# EngineeringModelBoard.net
KiCad netlist of a schematic drawn in EAGLE
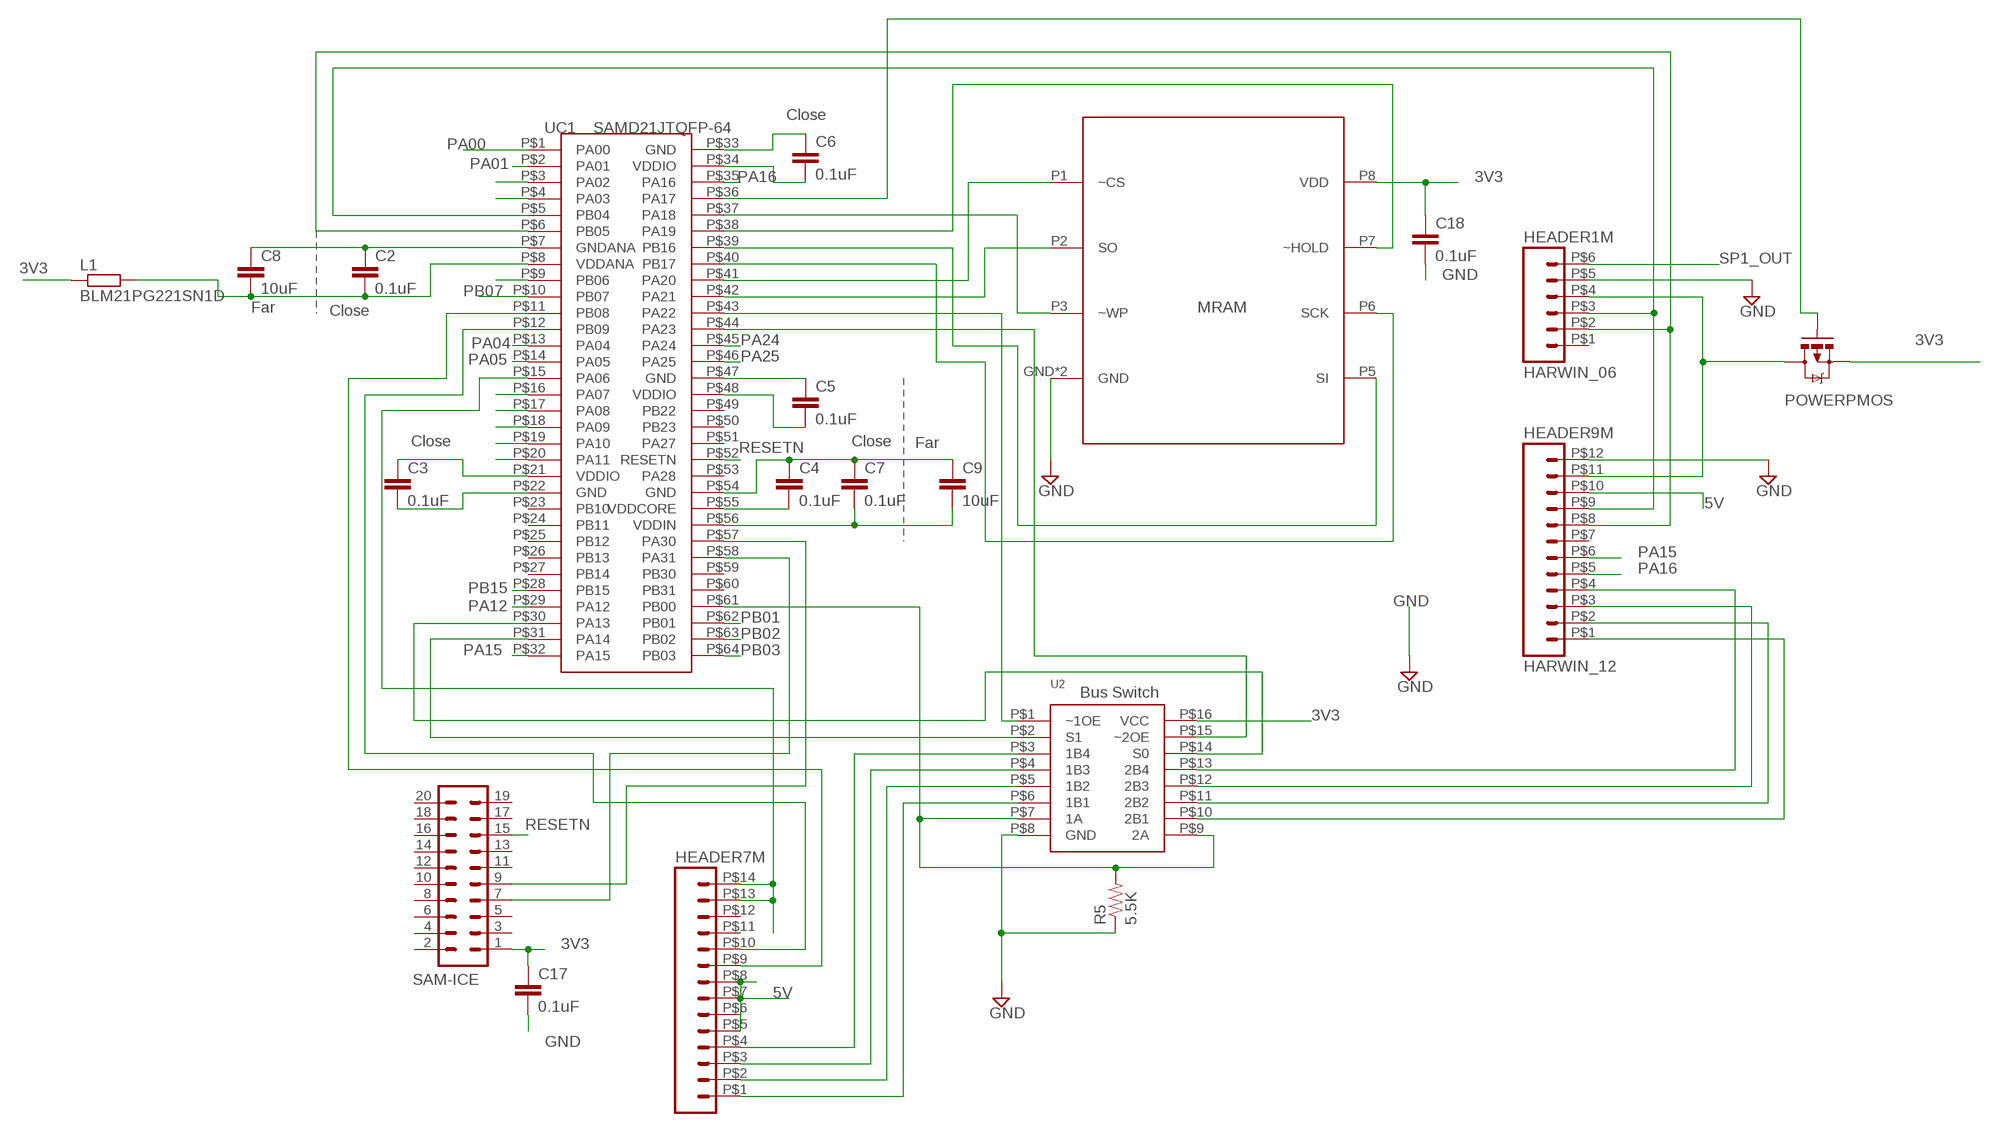
[diagram p0: schematic, sheet 1]
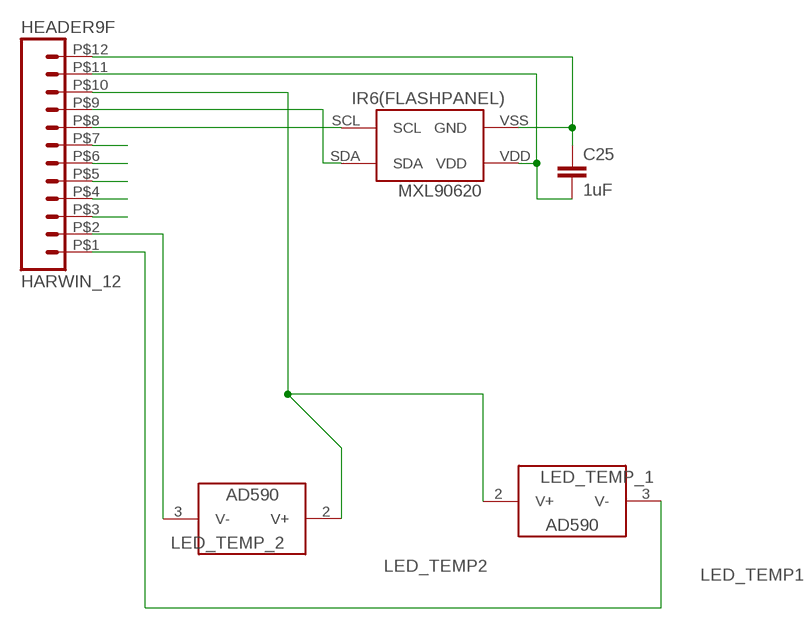
[diagram p1: schematic, sheet 2]
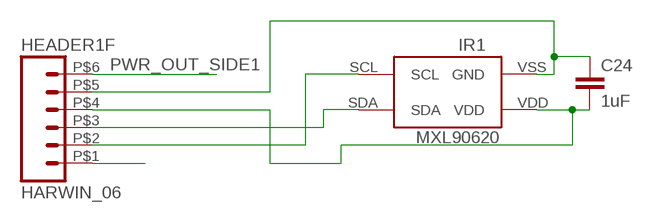
[diagram p2: schematic, sheet 3]
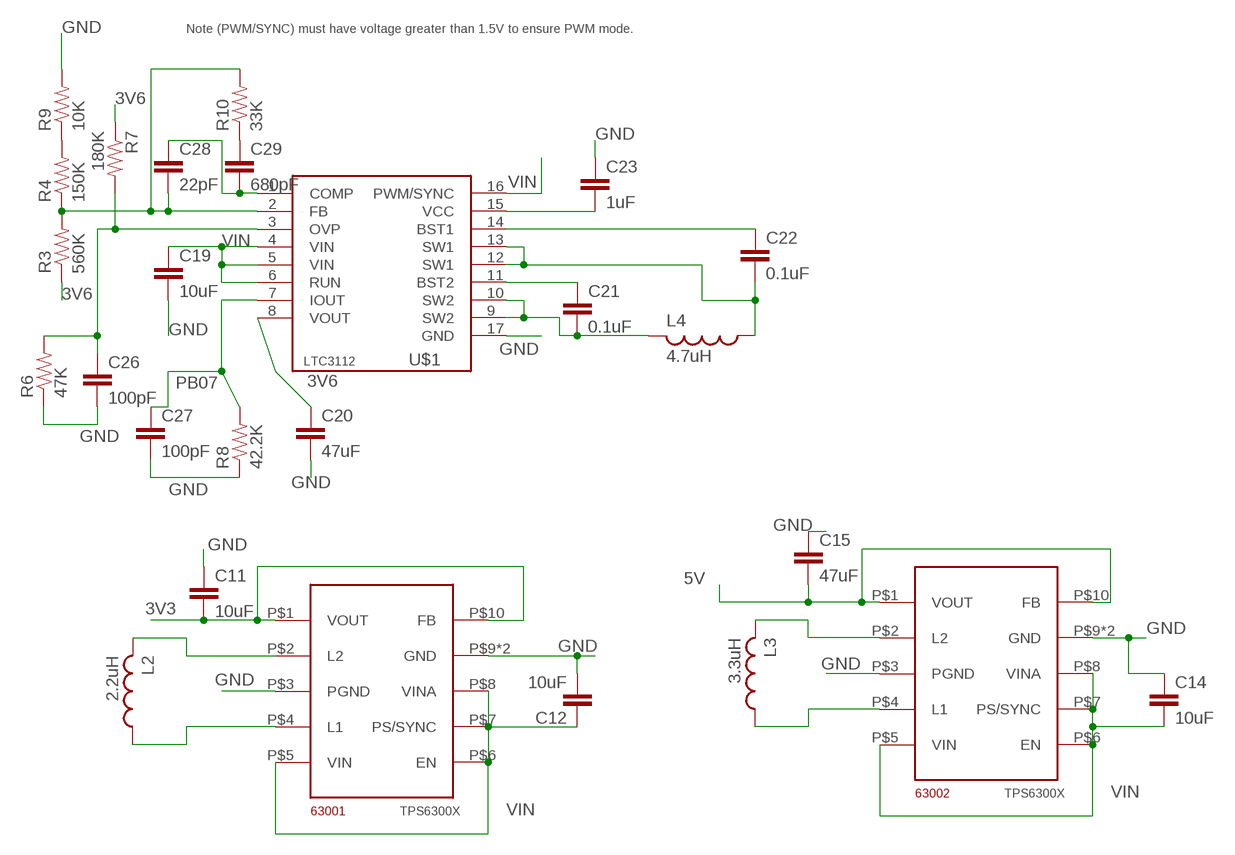
[diagram p3: schematic, sheet 4]
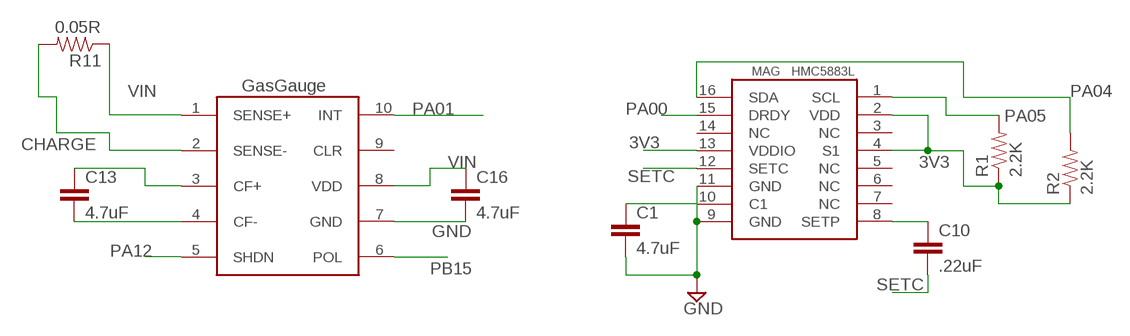
[diagram p4: schematic, sheet 5]
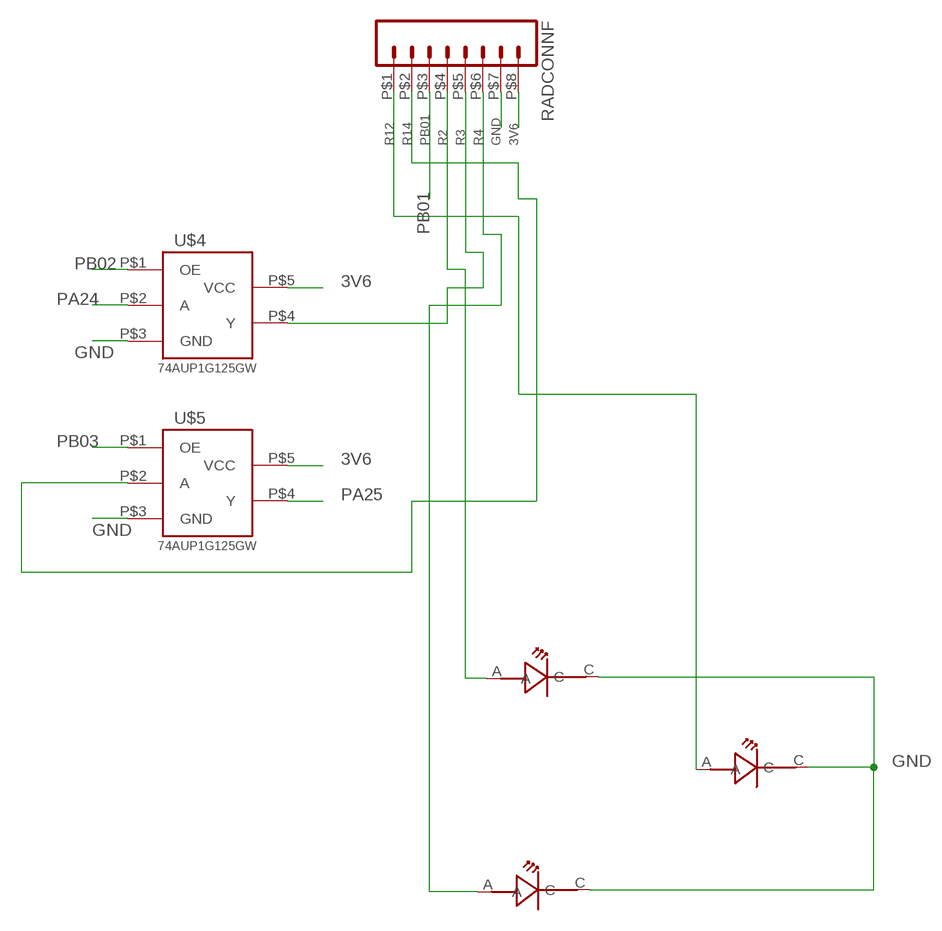
[diagram p5: schematic, sheet 6]
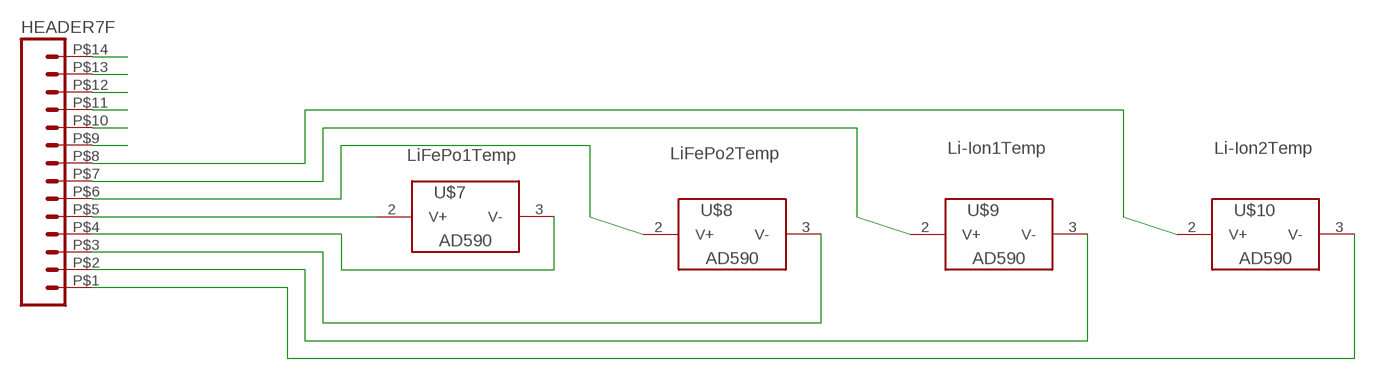
[diagram p6: schematic, sheet 7]

(export (version "E")
  (design (tool "Eeschema 10.0.6"))
  (components
    (comp (ref "C25")
      (value "1uF")
      (footprint "eagle-import:0805")
      (fields (field (name "MPN") "0805ZC105KAT2A"))
      (libsource (lib "eagle-import") (part "CAP0805"))
    )
    (comp (ref "HEADER9F")
      (value "HARWIN_12")
      (footprint "eagle-import:HARWIN_DATAMATE_12")
      (libsource (lib "eagle-import") (part "HARWIN_12"))
    )
    (comp (ref "IR6(FLASHPANEL)")
      (value "MXL90620")
      (footprint "eagle-import:MXL90620")
      (libsource (lib "eagle-import") (part "MXL90620"))
    )
    (comp (ref "LED_TEMP_1")
      (value "AD590-SOIC-8")
      (footprint "eagle-import:8SOIC")
      (fields (field (name "MPN") "AD590JRZ"))
      (libsource (lib "eagle-import") (part "AD590-SOIC-8"))
    )
    (comp (ref "LED_TEMP_2")
      (value "AD590-SOIC-8")
      (footprint "eagle-import:8SOIC")
      (fields (field (name "MPN") "AD590JRZ"))
      (libsource (lib "eagle-import") (part "AD590-SOIC-8"))
    )
    (comp (ref "RADCONNF")
      (value "HARWIN_08")
      (footprint "eagle-import:HARWIN_DATAMATE_08")
      (libsource (lib "eagle-import") (part "HARWIN_08"))
    )
    (comp (ref "U$4")
      (value "74AUP1G125GW")
      (footprint "eagle-import:TSSOP-5")
      (libsource (lib "eagle-import") (part "74AUP1G125GW"))
    )
    (comp (ref "U$5")
      (value "74AUP1G125GW")
      (footprint "eagle-import:TSSOP-5")
      (libsource (lib "eagle-import") (part "74AUP1G125GW"))
    )
    (comp (ref "U$11")
      (value "LT-T673-Q1R2-25-Z")
      (footprint "eagle-import:PLCC-2")
      (libsource (lib "eagle-import") (part "LT-T673-Q1R2-25-Z"))
    )
    (comp (ref "U$12")
      (value "LT-T673-Q1R2-25-Z")
      (footprint "eagle-import:PLCC-2")
      (libsource (lib "eagle-import") (part "LT-T673-Q1R2-25-Z"))
    )
    (comp (ref "U$13")
      (value "LT-T673-Q1R2-25-Z")
      (footprint "eagle-import:PLCC-2")
      (libsource (lib "eagle-import") (part "LT-T673-Q1R2-25-Z"))
    )
    (comp (ref "HEADER7F")
      (value "HARWIN_14")
      (footprint "eagle-import:HARWIN_DATAMATE_14")
      (libsource (lib "eagle-import") (part "HARWIN_14"))
    )
    (comp (ref "U$7")
      (value "AD590-SOIC-8")
      (footprint "eagle-import:8SOIC")
      (fields (field (name "MPN") "AD590JRZ"))
      (libsource (lib "eagle-import") (part "AD590-SOIC-8"))
    )
    (comp (ref "U$8")
      (value "AD590-SOIC-8")
      (footprint "eagle-import:8SOIC")
      (fields (field (name "MPN") "AD590JRZ"))
      (libsource (lib "eagle-import") (part "AD590-SOIC-8"))
    )
    (comp (ref "U$9")
      (value "AD590-SOIC-8")
      (footprint "eagle-import:8SOIC")
      (fields (field (name "MPN") "AD590JRZ"))
      (libsource (lib "eagle-import") (part "AD590-SOIC-8"))
    )
    (comp (ref "U$10")
      (value "AD590-SOIC-8")
      (footprint "eagle-import:8SOIC")
      (fields (field (name "MPN") "AD590JRZ"))
      (libsource (lib "eagle-import") (part "AD590-SOIC-8"))
    )
    (comp (ref "C1")
      (value "4.7uF")
      (footprint "eagle-import:0805")
      (fields (field (name "MF") "AVX CORPORATION") (field (name "MPN") "08056D475KAT2A"))
      (libsource (lib "eagle-import") (part "CAP0805"))
    )
    (comp (ref "C10")
      (value ".22uF")
      (footprint "eagle-import:0805")
      (fields (field (name "MF") "AVX CORPORATION") (field (name "MPN") "08053C224KAT2A"))
      (libsource (lib "eagle-import") (part "CAP0805"))
    )
    (comp (ref "C13")
      (value "4.7uF")
      (footprint "eagle-import:0805")
      (fields (field (name "MF") "AVX CORPORATION") (field (name "MPN") "08056D475KAT2A"))
      (libsource (lib "eagle-import") (part "CAP0805"))
    )
    (comp (ref "C16")
      (value "4.7uF")
      (footprint "eagle-import:0805")
      (fields (field (name "MF") "AVX CORPORATION") (field (name "MPN") "08056D475KAT2A"))
      (libsource (lib "eagle-import") (part "CAP0805"))
    )
    (comp (ref "MAG")
      (value "HMC5883L")
      (footprint "eagle-import:HMC5883L")
      (fields (field (name "MPN") "HMC5883L-TR"))
      (libsource (lib "eagle-import") (part "HMC5883L"))
    )
    (comp (ref "R1")
      (value "2.2K")
      (footprint "eagle-import:0805")
      (fields (field (name "MPN") "SR1-0805-222"))
      (libsource (lib "eagle-import") (part "RESISTOR"))
    )
    (comp (ref "R2")
      (value "2.2K")
      (footprint "eagle-import:0805")
      (fields (field (name "MPN") "SR1-0805-222"))
      (libsource (lib "eagle-import") (part "RESISTOR"))
    )
    (comp (ref "R11")
      (value "0.05R")
      (footprint "eagle-import:0805")
      (libsource (lib "eagle-import") (part "RESISTOR"))
    )
    (comp (ref "U$2")
      (value "LTC4150")
      (footprint "eagle-import:MSOP10")
      (fields (field (name "MPN") "LTC4150CMS#PBF"))
      (libsource (lib "eagle-import") (part "LTC4150"))
    )
    (comp (ref "C24")
      (value "1uF")
      (footprint "eagle-import:0805")
      (fields (field (name "MPN") "0805ZC105KAT2A"))
      (libsource (lib "eagle-import") (part "CAP0805"))
    )
    (comp (ref "HEADER1F")
      (value "HARWIN_06")
      (footprint "eagle-import:HARWIN_DATAMATE_6")
      (libsource (lib "eagle-import") (part "HARWIN_06"))
    )
    (comp (ref "IR1")
      (value "MXL90620")
      (footprint "eagle-import:MXL90620")
      (libsource (lib "eagle-import") (part "MXL90620"))
    )
    (comp (ref "C2")
      (value "0.1uF")
      (footprint "eagle-import:0805")
      (fields (field (name "MPN") "0603YC104JAT2A"))
      (libsource (lib "eagle-import") (part "CAP0805"))
    )
    (comp (ref "C3")
      (value "0.1uF")
      (footprint "eagle-import:0805")
      (fields (field (name "MPN") "0603YC104JAT2A"))
      (libsource (lib "eagle-import") (part "CAP0805"))
    )
    (comp (ref "C4")
      (value "0.1uF")
      (footprint "eagle-import:0805")
      (fields (field (name "MPN") "0603YC104JAT2A"))
      (libsource (lib "eagle-import") (part "CAP0805"))
    )
    (comp (ref "C5")
      (value "0.1uF")
      (footprint "eagle-import:0805")
      (fields (field (name "MPN") "0603YC104JAT2A"))
      (libsource (lib "eagle-import") (part "CAP0805"))
    )
    (comp (ref "C6")
      (value "0.1uF")
      (footprint "eagle-import:0805")
      (fields (field (name "MPN") "0603YC104JAT2A"))
      (libsource (lib "eagle-import") (part "CAP0805"))
    )
    (comp (ref "C7")
      (value "0.1uF")
      (footprint "eagle-import:0805")
      (fields (field (name "MPN") "0603YC104JAT2A"))
      (libsource (lib "eagle-import") (part "CAP0805"))
    )
    (comp (ref "C8")
      (value "10uF")
      (footprint "eagle-import:0805")
      (fields (field (name "MF") "AVX CORPORATION") (field (name "MPN") "08056D106KAT2A"))
      (libsource (lib "eagle-import") (part "CAP0805"))
    )
    (comp (ref "C9")
      (value "10uF")
      (footprint "eagle-import:0805")
      (fields (field (name "MF") "AVX CORPORATION") (field (name "MPN") "08056D106KAT2A"))
      (libsource (lib "eagle-import") (part "CAP0805"))
    )
    (comp (ref "C17")
      (value "0.1uF")
      (footprint "eagle-import:0805")
      (fields (field (name "MPN") "0603YC104JAT2A"))
      (libsource (lib "eagle-import") (part "CAP0805"))
    )
    (comp (ref "C18")
      (value "0.1uF")
      (footprint "eagle-import:0805")
      (fields (field (name "MPN") "0603YC104JAT2A"))
      (libsource (lib "eagle-import") (part "CAP0805"))
    )
    (comp (ref "HEADER1M")
      (value "HARWIN_06")
      (footprint "eagle-import:HARWIN_DATAMATE_6")
      (libsource (lib "eagle-import") (part "HARWIN_06"))
    )
    (comp (ref "HEADER7M")
      (value "HARWIN_14")
      (footprint "eagle-import:HARWIN_DATAMATE_14")
      (libsource (lib "eagle-import") (part "HARWIN_14"))
    )
    (comp (ref "HEADER9M")
      (value "HARWIN_12")
      (footprint "eagle-import:HARWIN_DATAMATE_12")
      (libsource (lib "eagle-import") (part "HARWIN_12"))
    )
    (comp (ref "L1")
      (value "BLM21PG221SN1D")
      (footprint "eagle-import:R0805")
      (libsource (lib "eagle-import") (part "R-EU_R0805"))
    )
    (comp (ref "R5")
      (value "5.5K")
      (footprint "eagle-import:0805")
      (libsource (lib "eagle-import") (part "RESISTOR"))
    )
    (comp (ref "SAM-ICE")
      (value "IDC_JTAG_CONNECTOR")
      (footprint "eagle-import:2X10")
      (libsource (lib "eagle-import") (part "IDC_JTAG_CONNECTOR"))
    )
    (comp (ref "U$3")
      (value "MRAM")
      (footprint "eagle-import:8PXMO-229")
      (libsource (lib "eagle-import") (part "MR25H10CDC"))
    )
    (comp (ref "U$14")
      (value "POWERPMOS")
      (footprint "eagle-import:SO08")
      (libsource (lib "eagle-import") (part "POWERPMOS"))
    )
    (comp (ref "U2")
      (value "SN74CBTLV3253")
      (footprint "eagle-import:SOIC16R")
      (libsource (lib "eagle-import") (part "SN74CBTLV3253"))
    )
    (comp (ref "UC1")
      (value "SAMD21JTQFP-64")
      (footprint "eagle-import:TQFP-64")
      (libsource (lib "eagle-import") (part "SAMD21JTQFP-64"))
    )
    (comp (ref "63001")
      (value "TPS6300X")
      (footprint "eagle-import:QFN10_POWERPAD")
      (libsource (lib "eagle-import") (part "TPS6300X"))
    )
    (comp (ref "63002")
      (value "TPS6300X")
      (footprint "eagle-import:QFN10_POWERPAD")
      (libsource (lib "eagle-import") (part "TPS6300X"))
    )
    (comp (ref "C11")
      (value "10uF")
      (footprint "eagle-import:0603-CAP")
      (libsource (lib "eagle-import") (part "CAP0603-CAP"))
    )
    (comp (ref "C12")
      (value "10uF")
      (footprint "eagle-import:0603-CAP")
      (libsource (lib "eagle-import") (part "CAP0603-CAP"))
    )
    (comp (ref "C14")
      (value "10uF")
      (footprint "eagle-import:0603-CAP")
      (fields (field (name "MPN") "C1608X5R1A225K080AC"))
      (libsource (lib "eagle-import") (part "CAP0603-CAP"))
    )
    (comp (ref "C15")
      (value "47uF")
      (footprint "eagle-import:0603-CAP")
      (fields (field (name "MPN") "EMK107B7474KA-T"))
      (libsource (lib "eagle-import") (part "CAP0603-CAP"))
    )
    (comp (ref "C19")
      (value "10uF")
      (footprint "eagle-import:0603-CAP")
      (libsource (lib "eagle-import") (part "CAP0603-CAP"))
    )
    (comp (ref "C20")
      (value "47uF")
      (footprint "eagle-import:0805")
      (fields (field (name "MPN") "EMK107B7474KA-T"))
      (libsource (lib "eagle-import") (part "CAP0805"))
    )
    (comp (ref "C21")
      (value "0.1uF")
      (footprint "eagle-import:0603-CAP")
      (fields (field (name "MPN") "0603YC104JAT2A"))
      (libsource (lib "eagle-import") (part "CAP0603-CAP"))
    )
    (comp (ref "C22")
      (value "0.1uF")
      (footprint "eagle-import:0603-CAP")
      (fields (field (name "MPN") "0603YC104JAT2A"))
      (libsource (lib "eagle-import") (part "CAP0603-CAP"))
    )
    (comp (ref "C23")
      (value "1uF")
      (footprint "eagle-import:0603-CAP")
      (libsource (lib "eagle-import") (part "CAP0603-CAP"))
    )
    (comp (ref "C26")
      (value "100pF")
      (footprint "eagle-import:0805")
      (fields (field (name "MF") "AVX CORPORATION") (field (name "MPN") "08051A101J4T4A"))
      (libsource (lib "eagle-import") (part "CAP0805"))
    )
    (comp (ref "C27")
      (value "100pF")
      (footprint "eagle-import:0805")
      (fields (field (name "MF") "AVX CORPORATION") (field (name "MPN") "08051A101J4T4A"))
      (libsource (lib "eagle-import") (part "CAP0805"))
    )
    (comp (ref "C28")
      (value "22pF")
      (footprint "eagle-import:0805")
      (fields (field (name "MF") "AVX CORPORATION") (field (name "MPN") "08051A220JAT2A"))
      (libsource (lib "eagle-import") (part "CAP0805"))
    )
    (comp (ref "C29")
      (value "680pF")
      (footprint "eagle-import:0805")
      (fields (field (name "MPN") "08055C681KAT2A"))
      (libsource (lib "eagle-import") (part "CAP0805"))
    )
    (comp (ref "L2")
      (value "2.2uH")
      (footprint "eagle-import:L3225M")
      (libsource (lib "eagle-import") (part "L-USL3225M"))
    )
    (comp (ref "L3")
      (value "3.3uH")
      (footprint "eagle-import:L3225M")
      (fields (field (name "MPN") "JMK212BJ335KG-T"))
      (libsource (lib "eagle-import") (part "L-USL3225M"))
    )
    (comp (ref "L4")
      (value "4.7uH")
      (footprint "eagle-import:L3225M")
      (libsource (lib "eagle-import") (part "L-USL3225M"))
    )
    (comp (ref "R3")
      (value "560K")
      (footprint "eagle-import:0805")
      (fields (field (name "MPN") "MC01W08051560K"))
      (libsource (lib "eagle-import") (part "RESISTOR"))
    )
    (comp (ref "R4")
      (value "150K")
      (footprint "eagle-import:0805")
      (libsource (lib "eagle-import") (part "RESISTOR"))
    )
    (comp (ref "R6")
      (value "47K")
      (footprint "eagle-import:0805")
      (libsource (lib "eagle-import") (part "RESISTOR"))
    )
    (comp (ref "R7")
      (value "180K")
      (footprint "eagle-import:0805")
      (fields (field (name "MPN") "ERJ-6GEYJ184V"))
      (libsource (lib "eagle-import") (part "RESISTOR"))
    )
    (comp (ref "R8")
      (value "42.2K")
      (footprint "eagle-import:0805")
      (libsource (lib "eagle-import") (part "RESISTOR"))
    )
    (comp (ref "R9")
      (value "10K")
      (footprint "eagle-import:0805")
      (libsource (lib "eagle-import") (part "RESISTOR"))
    )
    (comp (ref "R10")
      (value "33K")
      (footprint "eagle-import:0805")
      (libsource (lib "eagle-import") (part "RESISTOR"))
    )
    (comp (ref "U$1")
      (value "LTC3112")
      (footprint "eagle-import:DHD16")
      (fields (field (name "MPN") "LTC3112EFE#PBF"))
      (libsource (lib "eagle-import") (part "LTC3112"))
    )
  )
  (nets
    (net (code "1") (name "3V3") (class "Default")
      (node (ref "63001") (pin "P$1") (pinfunction "VOUT_P$1") (pintype "output"))
      (node (ref "63001") (pin "P$10") (pinfunction "FB_P$10") (pintype "input"))
      (node (ref "C11") (pin "2") (pinfunction "2_2") (pintype "passive"))
      (node (ref "C17") (pin "1") (pinfunction "1_1") (pintype "passive"))
      (node (ref "C18") (pin "1") (pinfunction "1_1") (pintype "passive"))
      (node (ref "C3") (pin "1") (pinfunction "1_1") (pintype "passive"))
      (node (ref "C5") (pin "2") (pinfunction "2_2") (pintype "passive"))
      (node (ref "C6") (pin "2") (pinfunction "2_2") (pintype "passive"))
      (node (ref "C7") (pin "2") (pinfunction "2_2") (pintype "passive"))
      (node (ref "C9") (pin "2") (pinfunction "2_2") (pintype "passive"))
      (node (ref "L1") (pin "1") (pinfunction "1_1") (pintype "passive"))
      (node (ref "MAG") (pin "13") (pinfunction "VDDIO_13") (pintype "bidirectional"))
      (node (ref "MAG") (pin "2") (pinfunction "VDD_2") (pintype "bidirectional"))
      (node (ref "MAG") (pin "4") (pinfunction "S1_4") (pintype "bidirectional"))
      (node (ref "R1") (pin "1") (pinfunction "1_1") (pintype "passive"))
      (node (ref "R2") (pin "1") (pinfunction "1_1") (pintype "passive"))
      (node (ref "SAM-ICE") (pin "1") (pinfunction "1_1") (pintype "passive"))
      (node (ref "U$14") (pin "1") (pinfunction "S_1") (pintype "passive"))
      (node (ref "U$14") (pin "2") (pinfunction "S_2") (pintype "passive"))
      (node (ref "U$14") (pin "3") (pinfunction "S_3") (pintype "passive"))
      (node (ref "U$3") (pin "P8") (pinfunction "VDD_P8") (pintype "bidirectional"))
      (node (ref "U2") (pin "P$16") (pinfunction "VCC_P$16") (pintype "bidirectional"))
      (node (ref "UC1") (pin "P$21") (pinfunction "VDDIO_P$21") (pintype "power_in"))
      (node (ref "UC1") (pin "P$34") (pinfunction "VDDIO_P$34") (pintype "power_in"))
      (node (ref "UC1") (pin "P$48") (pinfunction "VDDIO_P$48") (pintype "power_in"))
      (node (ref "UC1") (pin "P$56") (pinfunction "VDDIN_P$56") (pintype "power_in"))
    )
    (net (code "2") (name "3V6") (class "Default")
      (node (ref "C20") (pin "1") (pinfunction "1_1") (pintype "passive"))
      (node (ref "R3") (pin "1") (pinfunction "1_1") (pintype "passive"))
      (node (ref "R7") (pin "1") (pinfunction "1_1") (pintype "passive"))
      (node (ref "RADCONNF") (pin "P$8") (pinfunction "8_P$8") (pintype "passive"))
      (node (ref "U$1") (pin "8") (pinfunction "VOUT_8") (pintype "bidirectional"))
      (node (ref "U$4") (pin "P$5") (pinfunction "VCC_P$5") (pintype "bidirectional"))
      (node (ref "U$5") (pin "P$5") (pinfunction "VCC_P$5") (pintype "bidirectional"))
    )
    (net (code "3") (name "5V") (class "Default")
      (node (ref "63002") (pin "P$1") (pinfunction "VOUT_P$1") (pintype "output"))
      (node (ref "63002") (pin "P$10") (pinfunction "FB_P$10") (pintype "input"))
      (node (ref "C15") (pin "2") (pinfunction "2_2") (pintype "passive"))
      (node (ref "HEADER7M") (pin "P$5") (pinfunction "5_P$5") (pintype "passive"))
      (node (ref "HEADER7M") (pin "P$6") (pinfunction "6_P$6") (pintype "passive"))
      (node (ref "HEADER7M") (pin "P$7") (pinfunction "7_P$7") (pintype "passive"))
      (node (ref "HEADER7M") (pin "P$8") (pinfunction "8_P$8") (pintype "passive"))
      (node (ref "HEADER9M") (pin "P$10") (pinfunction "10_P$10") (pintype "passive"))
    )
    (net (code "4") (name "CHARGE") (class "Default")
      (node (ref "R11") (pin "2") (pinfunction "2_2") (pintype "passive"))
      (node (ref "U$2") (pin "2") (pinfunction "SENSE-_2") (pintype "bidirectional"))
    )
    (net (code "5") (name "GND") (class "Default")
      (node (ref "63001") (pin "P$3") (pinfunction "PGND_P$3") (pintype "input"))
      (node (ref "63001") (pin "P$9") (pinfunction "GND_P$9") (pintype "input"))
      (node (ref "63001") (pin "PAD") (pinfunction "GND_PAD") (pintype "input"))
      (node (ref "63002") (pin "P$3") (pinfunction "PGND_P$3") (pintype "input"))
      (node (ref "63002") (pin "P$9") (pinfunction "GND_P$9") (pintype "input"))
      (node (ref "63002") (pin "PAD") (pinfunction "GND_PAD") (pintype "input"))
      (node (ref "C1") (pin "2") (pinfunction "2_2") (pintype "passive"))
      (node (ref "C11") (pin "1") (pinfunction "1_1") (pintype "passive"))
      (node (ref "C12") (pin "2") (pinfunction "2_2") (pintype "passive"))
      (node (ref "C14") (pin "1") (pinfunction "1_1") (pintype "passive"))
      (node (ref "C15") (pin "1") (pinfunction "1_1") (pintype "passive"))
      (node (ref "C16") (pin "2") (pinfunction "2_2") (pintype "passive"))
      (node (ref "C17") (pin "2") (pinfunction "2_2") (pintype "passive"))
      (node (ref "C18") (pin "2") (pinfunction "2_2") (pintype "passive"))
      (node (ref "C19") (pin "2") (pinfunction "2_2") (pintype "passive"))
      (node (ref "C2") (pin "1") (pinfunction "1_1") (pintype "passive"))
      (node (ref "C20") (pin "2") (pinfunction "2_2") (pintype "passive"))
      (node (ref "C23") (pin "1") (pinfunction "1_1") (pintype "passive"))
      (node (ref "C26") (pin "2") (pinfunction "2_2") (pintype "passive"))
      (node (ref "C27") (pin "2") (pinfunction "2_2") (pintype "passive"))
      (node (ref "C4") (pin "1") (pinfunction "1_1") (pintype "passive"))
      (node (ref "C5") (pin "1") (pinfunction "1_1") (pintype "passive"))
      (node (ref "C6") (pin "1") (pinfunction "1_1") (pintype "passive"))
      (node (ref "C7") (pin "1") (pinfunction "1_1") (pintype "passive"))
      (node (ref "C8") (pin "1") (pinfunction "1_1") (pintype "passive"))
      (node (ref "C9") (pin "1") (pinfunction "1_1") (pintype "passive"))
      (node (ref "HEADER1M") (pin "P$5") (pinfunction "5_P$5") (pintype "passive"))
      (node (ref "HEADER9M") (pin "P$12") (pinfunction "12_P$12") (pintype "passive"))
      (node (ref "MAG") (pin "11") (pinfunction "GND_11") (pintype "bidirectional"))
      (node (ref "MAG") (pin "9") (pinfunction "GND_9") (pintype "bidirectional"))
      (node (ref "R5") (pin "1") (pinfunction "1_1") (pintype "passive"))
      (node (ref "R6") (pin "1") (pinfunction "1_1") (pintype "passive"))
      (node (ref "R8") (pin "1") (pinfunction "1_1") (pintype "passive"))
      (node (ref "R9") (pin "2") (pinfunction "2_2") (pintype "passive"))
      (node (ref "RADCONNF") (pin "P$7") (pinfunction "7_P$7") (pintype "passive"))
      (node (ref "U$1") (pin "17") (pinfunction "GND_17") (pintype "bidirectional"))
      (node (ref "U$11") (pin "C") (pinfunction "C_C") (pintype "bidirectional"))
      (node (ref "U$12") (pin "C") (pinfunction "C_C") (pintype "bidirectional"))
      (node (ref "U$13") (pin "C") (pinfunction "C_C") (pintype "bidirectional"))
      (node (ref "U$2") (pin "7") (pinfunction "GND_7") (pintype "bidirectional"))
      (node (ref "U$3") (pin "GND") (pinfunction "GND_GND") (pintype "bidirectional"))
      (node (ref "U$3") (pin "P4") (pinfunction "GND_P4") (pintype "bidirectional"))
      (node (ref "U$4") (pin "P$3") (pinfunction "GND_P$3") (pintype "bidirectional"))
      (node (ref "U$5") (pin "P$3") (pinfunction "GND_P$3") (pintype "bidirectional"))
      (node (ref "U2") (pin "P$8") (pinfunction "GND_P$8") (pintype "bidirectional"))
      (node (ref "UC1") (pin "P$33") (pinfunction "GND_P$33") (pintype "power_in"))
      (node (ref "UC1") (pin "P$47") (pinfunction "GND_P$47") (pintype "power_in"))
      (node (ref "UC1") (pin "P$54") (pinfunction "GND_P$54") (pintype "power_in"))
      (node (ref "UC1") (pin "P$7") (pinfunction "GNDANA_P$7") (pintype "power_in"))
    )
    (net (code "6") (name "Net-(63001-L1)") (class "Default")
      (node (ref "63001") (pin "P$4") (pinfunction "L1_P$4") (pintype "input"))
      (node (ref "L2") (pin "1") (pinfunction "1_1") (pintype "passive"))
    )
    (net (code "7") (name "Net-(63001-L2)") (class "Default")
      (node (ref "63001") (pin "P$2") (pinfunction "L2_P$2") (pintype "input"))
      (node (ref "L2") (pin "2") (pinfunction "2_2") (pintype "passive"))
    )
    (net (code "8") (name "Net-(63002-L1)") (class "Default")
      (node (ref "63002") (pin "P$4") (pinfunction "L1_P$4") (pintype "input"))
      (node (ref "L3") (pin "1") (pinfunction "1_1") (pintype "passive"))
    )
    (net (code "9") (name "Net-(63002-L2)") (class "Default")
      (node (ref "63002") (pin "P$2") (pinfunction "L2_P$2") (pintype "input"))
      (node (ref "L3") (pin "2") (pinfunction "2_2") (pintype "passive"))
    )
    (net (code "10") (name "Net-(C3-Pad2)") (class "Default")
      (node (ref "C3") (pin "2") (pinfunction "2_2") (pintype "passive"))
      (node (ref "UC1") (pin "P$22") (pinfunction "GND_P$22") (pintype "power_in"))
    )
    (net (code "11") (name "Net-(C21-Pad2)") (class "Default")
      (node (ref "C21") (pin "2") (pinfunction "2_2") (pintype "passive"))
      (node (ref "L4") (pin "2") (pinfunction "2_2") (pintype "passive"))
      (node (ref "U$1") (pin "10") (pinfunction "SW2_10") (pintype "bidirectional"))
      (node (ref "U$1") (pin "9") (pinfunction "SW2_9") (pintype "bidirectional"))
    )
    (net (code "12") (name "Net-(C22-Pad2)") (class "Default")
      (node (ref "C22") (pin "2") (pinfunction "2_2") (pintype "passive"))
      (node (ref "L4") (pin "1") (pinfunction "1_1") (pintype "passive"))
      (node (ref "U$1") (pin "12") (pinfunction "SW1_12") (pintype "bidirectional"))
      (node (ref "U$1") (pin "13") (pinfunction "SW1_13") (pintype "bidirectional"))
    )
    (net (code "13") (name "Net-(C29-Pad1)") (class "Default")
      (node (ref "C29") (pin "1") (pinfunction "1_1") (pintype "passive"))
      (node (ref "R10") (pin "1") (pinfunction "1_1") (pintype "passive"))
    )
    (net (code "14") (name "Net-(HEADER1F-2)") (class "Default")
      (node (ref "HEADER1F") (pin "P$2") (pinfunction "2_P$2") (pintype "passive"))
      (node (ref "IR1") (pin "SCL") (pinfunction "SCL_SCL") (pintype "bidirectional"))
    )
    (net (code "15") (name "Net-(HEADER1F-3)") (class "Default")
      (node (ref "HEADER1F") (pin "P$3") (pinfunction "3_P$3") (pintype "passive"))
      (node (ref "IR1") (pin "SDA") (pinfunction "SDA_SDA") (pintype "bidirectional"))
    )
    (net (code "16") (name "Net-(HEADER1F-4)") (class "Default")
      (node (ref "C24") (pin "2") (pinfunction "2_2") (pintype "passive"))
      (node (ref "HEADER1F") (pin "P$4") (pinfunction "4_P$4") (pintype "passive"))
      (node (ref "IR1") (pin "VDD") (pinfunction "VDD_VDD") (pintype "bidirectional"))
    )
    (net (code "17") (name "Net-(HEADER1F-5)") (class "Default")
      (node (ref "C24") (pin "1") (pinfunction "1_1") (pintype "passive"))
      (node (ref "HEADER1F") (pin "P$5") (pinfunction "5_P$5") (pintype "passive"))
      (node (ref "IR1") (pin "VSS") (pinfunction "GND_VSS") (pintype "bidirectional"))
    )
    (net (code "18") (name "Net-(HEADER1M-2)") (class "Default")
      (node (ref "HEADER1M") (pin "P$2") (pinfunction "2_P$2") (pintype "passive"))
      (node (ref "HEADER9M") (pin "P$8") (pinfunction "8_P$8") (pintype "passive"))
      (node (ref "UC1") (pin "P$6") (pinfunction "PB05_P$6") (pintype "bidirectional"))
    )
    (net (code "19") (name "Net-(HEADER1M-3)") (class "Default")
      (node (ref "HEADER1M") (pin "P$3") (pinfunction "3_P$3") (pintype "passive"))
      (node (ref "HEADER9M") (pin "P$9") (pinfunction "9_P$9") (pintype "passive"))
      (node (ref "UC1") (pin "P$5") (pinfunction "PB04_P$5") (pintype "bidirectional"))
    )
    (net (code "20") (name "Net-(HEADER1M-4)") (class "Default")
      (node (ref "HEADER1M") (pin "P$4") (pinfunction "4_P$4") (pintype "passive"))
      (node (ref "HEADER9M") (pin "P$11") (pinfunction "11_P$11") (pintype "passive"))
      (node (ref "U$14") (pin "5") (pinfunction "D_5") (pintype "passive"))
      (node (ref "U$14") (pin "6") (pinfunction "D_6") (pintype "passive"))
      (node (ref "U$14") (pin "7") (pinfunction "D_7") (pintype "passive"))
      (node (ref "U$14") (pin "8") (pinfunction "D_8") (pintype "passive"))
    )
    (net (code "21") (name "Net-(HEADER7F-1)") (class "Default")
      (node (ref "HEADER7F") (pin "P$1") (pinfunction "1_P$1") (pintype "passive"))
      (node (ref "U$10") (pin "3") (pinfunction "V-_3") (pintype "bidirectional"))
    )
    (net (code "22") (name "Net-(HEADER7F-2)") (class "Default")
      (node (ref "HEADER7F") (pin "P$2") (pinfunction "2_P$2") (pintype "passive"))
      (node (ref "U$9") (pin "3") (pinfunction "V-_3") (pintype "bidirectional"))
    )
    (net (code "23") (name "Net-(HEADER7F-3)") (class "Default")
      (node (ref "HEADER7F") (pin "P$3") (pinfunction "3_P$3") (pintype "passive"))
      (node (ref "U$8") (pin "3") (pinfunction "V-_3") (pintype "bidirectional"))
    )
    (net (code "24") (name "Net-(HEADER7F-4)") (class "Default")
      (node (ref "HEADER7F") (pin "P$4") (pinfunction "4_P$4") (pintype "passive"))
      (node (ref "U$7") (pin "3") (pinfunction "V-_3") (pintype "bidirectional"))
    )
    (net (code "25") (name "Net-(HEADER7F-5)") (class "Default")
      (node (ref "HEADER7F") (pin "P$5") (pinfunction "5_P$5") (pintype "passive"))
      (node (ref "U$7") (pin "2") (pinfunction "V+_2") (pintype "bidirectional"))
    )
    (net (code "26") (name "Net-(HEADER7F-6)") (class "Default")
      (node (ref "HEADER7F") (pin "P$6") (pinfunction "6_P$6") (pintype "passive"))
      (node (ref "U$8") (pin "2") (pinfunction "V+_2") (pintype "bidirectional"))
    )
    (net (code "27") (name "Net-(HEADER7F-7)") (class "Default")
      (node (ref "HEADER7F") (pin "P$7") (pinfunction "7_P$7") (pintype "passive"))
      (node (ref "U$9") (pin "2") (pinfunction "V+_2") (pintype "bidirectional"))
    )
    (net (code "28") (name "Net-(HEADER7F-8)") (class "Default")
      (node (ref "HEADER7F") (pin "P$8") (pinfunction "8_P$8") (pintype "passive"))
      (node (ref "U$10") (pin "2") (pinfunction "V+_2") (pintype "bidirectional"))
    )
    (net (code "29") (name "Net-(HEADER7M-1)") (class "Default")
      (node (ref "HEADER7M") (pin "P$1") (pinfunction "1_P$1") (pintype "passive"))
      (node (ref "U2") (pin "P$6") (pinfunction "1B1_P$6") (pintype "bidirectional"))
    )
    (net (code "30") (name "Net-(HEADER7M-2)") (class "Default")
      (node (ref "HEADER7M") (pin "P$2") (pinfunction "2_P$2") (pintype "passive"))
      (node (ref "U2") (pin "P$5") (pinfunction "1B2_P$5") (pintype "bidirectional"))
    )
    (net (code "31") (name "Net-(HEADER7M-3)") (class "Default")
      (node (ref "HEADER7M") (pin "P$3") (pinfunction "3_P$3") (pintype "passive"))
      (node (ref "U2") (pin "P$4") (pinfunction "1B3_P$4") (pintype "bidirectional"))
    )
    (net (code "32") (name "Net-(HEADER7M-4)") (class "Default")
      (node (ref "HEADER7M") (pin "P$4") (pinfunction "4_P$4") (pintype "passive"))
      (node (ref "U2") (pin "P$3") (pinfunction "1B4_P$3") (pintype "bidirectional"))
    )
    (net (code "33") (name "Net-(HEADER7M-9)") (class "Default")
      (node (ref "HEADER7M") (pin "P$9") (pinfunction "9_P$9") (pintype "passive"))
      (node (ref "UC1") (pin "P$11") (pinfunction "PB08_P$11") (pintype "bidirectional"))
    )
    (net (code "34") (name "Net-(HEADER7M-10)") (class "Default")
      (node (ref "HEADER7M") (pin "P$10") (pinfunction "10_P$10") (pintype "passive"))
      (node (ref "UC1") (pin "P$12") (pinfunction "PB09_P$12") (pintype "bidirectional"))
    )
    (net (code "35") (name "Net-(HEADER7M-13)") (class "Default")
      (node (ref "HEADER7M") (pin "P$13") (pinfunction "13_P$13") (pintype "passive"))
      (node (ref "HEADER7M") (pin "P$14") (pinfunction "14_P$14") (pintype "passive"))
      (node (ref "UC1") (pin "P$15") (pinfunction "PA06_P$15") (pintype "bidirectional"))
    )
    (net (code "36") (name "Net-(HEADER9F-1)") (class "Default")
      (node (ref "HEADER9F") (pin "P$1") (pinfunction "1_P$1") (pintype "passive"))
      (node (ref "LED_TEMP_1") (pin "3") (pinfunction "V-_3") (pintype "bidirectional"))
    )
    (net (code "37") (name "Net-(HEADER9F-2)") (class "Default")
      (node (ref "HEADER9F") (pin "P$2") (pinfunction "2_P$2") (pintype "passive"))
      (node (ref "LED_TEMP_2") (pin "3") (pinfunction "V-_3") (pintype "bidirectional"))
    )
    (net (code "38") (name "Net-(HEADER9F-8)") (class "Default")
      (node (ref "HEADER9F") (pin "P$8") (pinfunction "8_P$8") (pintype "passive"))
      (node (ref "IR6(FLASHPANEL)") (pin "SCL") (pinfunction "SCL_SCL") (pintype "bidirectional"))
    )
    (net (code "39") (name "Net-(HEADER9F-9)") (class "Default")
      (node (ref "HEADER9F") (pin "P$9") (pinfunction "9_P$9") (pintype "passive"))
      (node (ref "IR6(FLASHPANEL)") (pin "SDA") (pinfunction "SDA_SDA") (pintype "bidirectional"))
    )
    (net (code "40") (name "Net-(HEADER9F-10)") (class "Default")
      (node (ref "HEADER9F") (pin "P$10") (pinfunction "10_P$10") (pintype "passive"))
      (node (ref "LED_TEMP_1") (pin "2") (pinfunction "V+_2") (pintype "bidirectional"))
      (node (ref "LED_TEMP_2") (pin "2") (pinfunction "V+_2") (pintype "bidirectional"))
    )
    (net (code "41") (name "Net-(HEADER9F-11)") (class "Default")
      (node (ref "C25") (pin "2") (pinfunction "2_2") (pintype "passive"))
      (node (ref "HEADER9F") (pin "P$11") (pinfunction "11_P$11") (pintype "passive"))
      (node (ref "IR6(FLASHPANEL)") (pin "VDD") (pinfunction "VDD_VDD") (pintype "bidirectional"))
    )
    (net (code "42") (name "Net-(HEADER9F-12)") (class "Default")
      (node (ref "C25") (pin "1") (pinfunction "1_1") (pintype "passive"))
      (node (ref "HEADER9F") (pin "P$12") (pinfunction "12_P$12") (pintype "passive"))
      (node (ref "IR6(FLASHPANEL)") (pin "VSS") (pinfunction "GND_VSS") (pintype "bidirectional"))
    )
    (net (code "43") (name "Net-(HEADER9M-1)") (class "Default")
      (node (ref "HEADER9M") (pin "P$1") (pinfunction "1_P$1") (pintype "passive"))
      (node (ref "U2") (pin "P$10") (pinfunction "2B1_P$10") (pintype "bidirectional"))
    )
    (net (code "44") (name "Net-(HEADER9M-2)") (class "Default")
      (node (ref "HEADER9M") (pin "P$2") (pinfunction "2_P$2") (pintype "passive"))
      (node (ref "U2") (pin "P$11") (pinfunction "2B2_P$11") (pintype "bidirectional"))
    )
    (net (code "45") (name "Net-(HEADER9M-3)") (class "Default")
      (node (ref "HEADER9M") (pin "P$3") (pinfunction "3_P$3") (pintype "passive"))
      (node (ref "U2") (pin "P$12") (pinfunction "2B3_P$12") (pintype "bidirectional"))
    )
    (net (code "46") (name "Net-(HEADER9M-4)") (class "Default")
      (node (ref "HEADER9M") (pin "P$4") (pinfunction "4_P$4") (pintype "passive"))
      (node (ref "U2") (pin "P$13") (pinfunction "2B4_P$13") (pintype "bidirectional"))
    )
    (net (code "47") (name "Net-(MAG-C1)") (class "Default")
      (node (ref "C1") (pin "1") (pinfunction "1_1") (pintype "passive"))
      (node (ref "MAG") (pin "10") (pinfunction "C1_10") (pintype "bidirectional"))
    )
    (net (code "48") (name "Net-(MAG-SETP)") (class "Default")
      (node (ref "C10") (pin "1") (pinfunction "1_1") (pintype "passive"))
      (node (ref "MAG") (pin "8") (pinfunction "SETP_8") (pintype "bidirectional"))
    )
    (net (code "49") (name "Net-(R4-Pad2)") (class "Default")
      (node (ref "R4") (pin "2") (pinfunction "2_2") (pintype "passive"))
      (node (ref "R9") (pin "1") (pinfunction "1_1") (pintype "passive"))
    )
    (net (code "50") (name "Net-(U$1-BST1)") (class "Default")
      (node (ref "C22") (pin "1") (pinfunction "1_1") (pintype "passive"))
      (node (ref "U$1") (pin "14") (pinfunction "BST1_14") (pintype "bidirectional"))
    )
    (net (code "51") (name "Net-(U$1-BST2)") (class "Default")
      (node (ref "C21") (pin "1") (pinfunction "1_1") (pintype "passive"))
      (node (ref "U$1") (pin "11") (pinfunction "BST2_11") (pintype "bidirectional"))
    )
    (net (code "52") (name "Net-(U$1-COMP)") (class "Default")
      (node (ref "C28") (pin "1") (pinfunction "1_1") (pintype "passive"))
      (node (ref "C29") (pin "2") (pinfunction "2_2") (pintype "passive"))
      (node (ref "U$1") (pin "1") (pinfunction "COMP_1") (pintype "bidirectional"))
    )
    (net (code "53") (name "Net-(U$1-FB)") (class "Default")
      (node (ref "C28") (pin "2") (pinfunction "2_2") (pintype "passive"))
      (node (ref "R10") (pin "2") (pinfunction "2_2") (pintype "passive"))
      (node (ref "R3") (pin "2") (pinfunction "2_2") (pintype "passive"))
      (node (ref "R4") (pin "1") (pinfunction "1_1") (pintype "passive"))
      (node (ref "U$1") (pin "2") (pinfunction "FB_2") (pintype "bidirectional"))
    )
    (net (code "54") (name "Net-(U$1-OVP)") (class "Default")
      (node (ref "C26") (pin "1") (pinfunction "1_1") (pintype "passive"))
      (node (ref "R6") (pin "2") (pinfunction "2_2") (pintype "passive"))
      (node (ref "R7") (pin "2") (pinfunction "2_2") (pintype "passive"))
      (node (ref "U$1") (pin "3") (pinfunction "OVP_3") (pintype "bidirectional"))
    )
    (net (code "55") (name "Net-(U$1-VCC)") (class "Default")
      (node (ref "C23") (pin "2") (pinfunction "2_2") (pintype "passive"))
      (node (ref "U$1") (pin "15") (pinfunction "VCC_15") (pintype "bidirectional"))
    )
    (net (code "56") (name "Net-(U$2-CF+)") (class "Default")
      (node (ref "C13") (pin "1") (pinfunction "1_1") (pintype "passive"))
      (node (ref "U$2") (pin "3") (pinfunction "CF+_3") (pintype "bidirectional"))
    )
    (net (code "57") (name "Net-(U$2-CF-)") (class "Default")
      (node (ref "C13") (pin "2") (pinfunction "2_2") (pintype "passive"))
      (node (ref "U$2") (pin "4") (pinfunction "CF-_4") (pintype "bidirectional"))
    )
    (net (code "58") (name "Net-(U$3-SCK)") (class "Default")
      (node (ref "U$3") (pin "P6") (pinfunction "SCK_P6") (pintype "bidirectional"))
      (node (ref "UC1") (pin "P$40") (pinfunction "PB17_P$40") (pintype "bidirectional"))
    )
    (net (code "59") (name "Net-(U$3-SI)") (class "Default")
      (node (ref "U$3") (pin "P5") (pinfunction "SI_P5") (pintype "bidirectional"))
      (node (ref "UC1") (pin "P$39") (pinfunction "PB16_P$39") (pintype "bidirectional"))
    )
    (net (code "60") (name "Net-(U$3-SO)") (class "Default")
      (node (ref "U$3") (pin "P2") (pinfunction "SO_P2") (pintype "bidirectional"))
      (node (ref "UC1") (pin "P$42") (pinfunction "PA21_P$42") (pintype "bidirectional"))
    )
    (net (code "61") (name "Net-(U$3-~{CS})") (class "Default")
      (node (ref "U$3") (pin "P1") (pinfunction "~{CS}_P1") (pintype "bidirectional"))
      (node (ref "UC1") (pin "P$41") (pinfunction "PA20_P$41") (pintype "bidirectional"))
    )
    (net (code "62") (name "Net-(U$3-~{HOLD})") (class "Default")
      (node (ref "U$3") (pin "P7") (pinfunction "~{HOLD}_P7") (pintype "bidirectional"))
      (node (ref "UC1") (pin "P$38") (pinfunction "PA19_P$38") (pintype "bidirectional"))
    )
    (net (code "63") (name "Net-(U$3-~{WP})") (class "Default")
      (node (ref "U$3") (pin "P3") (pinfunction "~{WP}_P3") (pintype "bidirectional"))
      (node (ref "UC1") (pin "P$37") (pinfunction "PA18_P$37") (pintype "bidirectional"))
    )
    (net (code "64") (name "Net-(U$14-G)") (class "Default")
      (node (ref "U$14") (pin "4") (pinfunction "G_4") (pintype "passive"))
      (node (ref "UC1") (pin "P$36") (pinfunction "PA17_P$36") (pintype "bidirectional"))
    )
    (net (code "65") (name "Net-(U2-1A)") (class "Default")
      (node (ref "R5") (pin "2") (pinfunction "2_2") (pintype "passive"))
      (node (ref "U2") (pin "P$7") (pinfunction "1A_P$7") (pintype "bidirectional"))
      (node (ref "U2") (pin "P$9") (pinfunction "2A_P$9") (pintype "bidirectional"))
      (node (ref "UC1") (pin "P$61") (pinfunction "PB00_P$61") (pintype "bidirectional"))
    )
    (net (code "66") (name "Net-(U2-S0)") (class "Default")
      (node (ref "U2") (pin "P$14") (pinfunction "S0_P$14") (pintype "bidirectional"))
      (node (ref "UC1") (pin "P$30") (pinfunction "PA13_P$30") (pintype "bidirectional"))
    )
    (net (code "67") (name "Net-(U2-S1)") (class "Default")
      (node (ref "U2") (pin "P$2") (pinfunction "S1_P$2") (pintype "bidirectional"))
      (node (ref "UC1") (pin "P$31") (pinfunction "PA14_P$31") (pintype "bidirectional"))
    )
    (net (code "68") (name "Net-(U2-~{1OE})") (class "Default")
      (node (ref "U2") (pin "P$1") (pinfunction "~{1OE}_P$1") (pintype "bidirectional"))
      (node (ref "UC1") (pin "P$43") (pinfunction "PA22_P$43") (pintype "bidirectional"))
    )
    (net (code "69") (name "Net-(U2-~{2OE})") (class "Default")
      (node (ref "U2") (pin "P$15") (pinfunction "~{2OE}_P$15") (pintype "bidirectional"))
      (node (ref "UC1") (pin "P$44") (pinfunction "PA23_P$44") (pintype "bidirectional"))
    )
    (net (code "70") (name "Net-(UC1-PA30)") (class "Default")
      (node (ref "SAM-ICE") (pin "9") (pinfunction "9_9") (pintype "passive"))
      (node (ref "UC1") (pin "P$57") (pinfunction "PA30_P$57") (pintype "bidirectional"))
    )
    (net (code "71") (name "Net-(UC1-PA31)") (class "Default")
      (node (ref "SAM-ICE") (pin "7") (pinfunction "7_7") (pintype "passive"))
      (node (ref "UC1") (pin "P$58") (pinfunction "PA31_P$58") (pintype "bidirectional"))
    )
    (net (code "72") (name "Net-(UC1-VDDANA)") (class "Default")
      (node (ref "C2") (pin "2") (pinfunction "2_2") (pintype "passive"))
      (node (ref "C8") (pin "2") (pinfunction "2_2") (pintype "passive"))
      (node (ref "L1") (pin "2") (pinfunction "2_2") (pintype "passive"))
      (node (ref "UC1") (pin "P$8") (pinfunction "VDDANA_P$8") (pintype "power_in"))
    )
    (net (code "73") (name "Net-(UC1-VDDCORE)") (class "Default")
      (node (ref "C4") (pin "2") (pinfunction "2_2") (pintype "passive"))
      (node (ref "UC1") (pin "P$55") (pinfunction "VDDCORE_P$55") (pintype "power_in"))
    )
    (net (code "74") (name "PA00") (class "Default")
      (node (ref "MAG") (pin "15") (pinfunction "DRDY_15") (pintype "bidirectional"))
      (node (ref "UC1") (pin "P$1") (pinfunction "PA00_P$1") (pintype "bidirectional"))
    )
    (net (code "75") (name "PA01") (class "Default")
      (node (ref "U$2") (pin "10") (pinfunction "INT_10") (pintype "bidirectional"))
      (node (ref "UC1") (pin "P$2") (pinfunction "PA01_P$2") (pintype "bidirectional"))
    )
    (net (code "76") (name "PA04") (class "Default")
      (node (ref "MAG") (pin "16") (pinfunction "SDA_16") (pintype "bidirectional"))
      (node (ref "R2") (pin "2") (pinfunction "2_2") (pintype "passive"))
      (node (ref "UC1") (pin "P$13") (pinfunction "PA04_P$13") (pintype "bidirectional"))
    )
    (net (code "77") (name "PA05") (class "Default")
      (node (ref "MAG") (pin "1") (pinfunction "SCL_1") (pintype "bidirectional"))
      (node (ref "R1") (pin "2") (pinfunction "2_2") (pintype "passive"))
      (node (ref "UC1") (pin "P$14") (pinfunction "PA05_P$14") (pintype "bidirectional"))
    )
    (net (code "78") (name "PA12") (class "Default")
      (node (ref "U$2") (pin "5") (pinfunction "SHDN_5") (pintype "bidirectional"))
      (node (ref "UC1") (pin "P$29") (pinfunction "PA12_P$29") (pintype "bidirectional"))
    )
    (net (code "79") (name "PA15") (class "Default")
      (node (ref "HEADER9M") (pin "P$6") (pinfunction "6_P$6") (pintype "passive"))
      (node (ref "UC1") (pin "P$32") (pinfunction "PA15_P$32") (pintype "bidirectional"))
    )
    (net (code "80") (name "PA16") (class "Default")
      (node (ref "HEADER9M") (pin "P$5") (pinfunction "5_P$5") (pintype "passive"))
      (node (ref "UC1") (pin "P$35") (pinfunction "PA16_P$35") (pintype "bidirectional"))
    )
    (net (code "81") (name "PA24") (class "Default")
      (node (ref "U$4") (pin "P$2") (pinfunction "A_P$2") (pintype "bidirectional"))
      (node (ref "UC1") (pin "P$45") (pinfunction "PA24_P$45") (pintype "bidirectional"))
    )
    (net (code "82") (name "PA25") (class "Default")
      (node (ref "U$5") (pin "P$4") (pinfunction "Y_P$4") (pintype "bidirectional"))
      (node (ref "UC1") (pin "P$46") (pinfunction "PA25_P$46") (pintype "bidirectional"))
    )
    (net (code "83") (name "PB01") (class "Default")
      (node (ref "RADCONNF") (pin "P$3") (pinfunction "3_P$3") (pintype "passive"))
      (node (ref "UC1") (pin "P$62") (pinfunction "PB01_P$62") (pintype "bidirectional"))
    )
    (net (code "84") (name "PB02") (class "Default")
      (node (ref "U$4") (pin "P$1") (pinfunction "OE_P$1") (pintype "bidirectional"))
      (node (ref "UC1") (pin "P$63") (pinfunction "PB02_P$63") (pintype "bidirectional"))
    )
    (net (code "85") (name "PB03") (class "Default")
      (node (ref "U$5") (pin "P$1") (pinfunction "OE_P$1") (pintype "bidirectional"))
      (node (ref "UC1") (pin "P$64") (pinfunction "PB03_P$64") (pintype "bidirectional"))
    )
    (net (code "86") (name "PB07") (class "Default")
      (node (ref "C27") (pin "1") (pinfunction "1_1") (pintype "passive"))
      (node (ref "R8") (pin "2") (pinfunction "2_2") (pintype "passive"))
      (node (ref "U$1") (pin "7") (pinfunction "IOUT_7") (pintype "bidirectional"))
      (node (ref "UC1") (pin "P$10") (pinfunction "PB07_P$10") (pintype "bidirectional"))
    )
    (net (code "87") (name "PB15") (class "Default")
      (node (ref "U$2") (pin "6") (pinfunction "POL_6") (pintype "bidirectional"))
      (node (ref "UC1") (pin "P$28") (pinfunction "PB15_P$28") (pintype "bidirectional"))
    )
    (net (code "88") (name "PWR_OUT_SIDE1") (class "Default")
      (node (ref "HEADER1F") (pin "P$6") (pinfunction "6_P$6") (pintype "passive"))
    )
    (net (code "89") (name "R2") (class "Default")
      (node (ref "RADCONNF") (pin "P$4") (pinfunction "4_P$4") (pintype "passive"))
      (node (ref "U$13") (pin "A") (pinfunction "A_A") (pintype "bidirectional"))
    )
    (net (code "90") (name "R3") (class "Default")
      (node (ref "RADCONNF") (pin "P$5") (pinfunction "5_P$5") (pintype "passive"))
      (node (ref "U$4") (pin "P$4") (pinfunction "Y_P$4") (pintype "bidirectional"))
    )
    (net (code "91") (name "R4") (class "Default")
      (node (ref "RADCONNF") (pin "P$6") (pinfunction "6_P$6") (pintype "passive"))
      (node (ref "U$12") (pin "A") (pinfunction "A_A") (pintype "bidirectional"))
    )
    (net (code "92") (name "R12") (class "Default")
      (node (ref "RADCONNF") (pin "P$1") (pinfunction "1_P$1") (pintype "passive"))
      (node (ref "U$11") (pin "A") (pinfunction "A_A") (pintype "bidirectional"))
    )
    (net (code "93") (name "R14") (class "Default")
      (node (ref "RADCONNF") (pin "P$2") (pinfunction "2_P$2") (pintype "passive"))
      (node (ref "U$5") (pin "P$2") (pinfunction "A_P$2") (pintype "bidirectional"))
    )
    (net (code "94") (name "RESETN") (class "Default")
      (node (ref "SAM-ICE") (pin "15") (pinfunction "15_15") (pintype "passive"))
      (node (ref "UC1") (pin "P$52") (pinfunction "RESETN_P$52") (pintype "input"))
    )
    (net (code "95") (name "SETC") (class "Default")
      (node (ref "C10") (pin "2") (pinfunction "2_2") (pintype "passive"))
      (node (ref "MAG") (pin "12") (pinfunction "SETC_12") (pintype "bidirectional"))
    )
    (net (code "96") (name "SP1_OUT") (class "Default")
      (node (ref "HEADER1M") (pin "P$6") (pinfunction "6_P$6") (pintype "passive"))
    )
    (net (code "97") (name "VIN") (class "Default")
      (node (ref "63001") (pin "P$5") (pinfunction "VIN_P$5") (pintype "input"))
      (node (ref "63001") (pin "P$6") (pinfunction "EN_P$6") (pintype "input"))
      (node (ref "63001") (pin "P$7") (pinfunction "PS/SYNC_P$7") (pintype "input"))
      (node (ref "63001") (pin "P$8") (pinfunction "VINA_P$8") (pintype "input"))
      (node (ref "63002") (pin "P$5") (pinfunction "VIN_P$5") (pintype "input"))
      (node (ref "63002") (pin "P$6") (pinfunction "EN_P$6") (pintype "input"))
      (node (ref "63002") (pin "P$7") (pinfunction "PS/SYNC_P$7") (pintype "input"))
      (node (ref "63002") (pin "P$8") (pinfunction "VINA_P$8") (pintype "input"))
      (node (ref "C12") (pin "1") (pinfunction "1_1") (pintype "passive"))
      (node (ref "C14") (pin "2") (pinfunction "2_2") (pintype "passive"))
      (node (ref "C16") (pin "1") (pinfunction "1_1") (pintype "passive"))
      (node (ref "C19") (pin "1") (pinfunction "1_1") (pintype "passive"))
      (node (ref "R11") (pin "1") (pinfunction "1_1") (pintype "passive"))
      (node (ref "U$1") (pin "16") (pinfunction "PWM/SYNC_16") (pintype "bidirectional"))
      (node (ref "U$1") (pin "4") (pinfunction "VIN_4") (pintype "bidirectional"))
      (node (ref "U$1") (pin "5") (pinfunction "VIN_5") (pintype "bidirectional"))
      (node (ref "U$1") (pin "6") (pinfunction "RUN_6") (pintype "bidirectional"))
      (node (ref "U$2") (pin "1") (pinfunction "SENSE+_1") (pintype "bidirectional"))
      (node (ref "U$2") (pin "8") (pinfunction "VDD_8") (pintype "bidirectional"))
    )
    (net (code "98") (name "unconnected-(HEADER1F-1-PadP$1)") (class "Default")
      (node (ref "HEADER1F") (pin "P$1") (pinfunction "1_P$1") (pintype "passive"))
    )
    (net (code "99") (name "unconnected-(HEADER1M-1-PadP$1)") (class "Default")
      (node (ref "HEADER1M") (pin "P$1") (pinfunction "1_P$1") (pintype "passive"))
    )
    (net (code "100") (name "unconnected-(HEADER7F-9-PadP$9)") (class "Default")
      (node (ref "HEADER7F") (pin "P$9") (pinfunction "9_P$9") (pintype "passive"))
    )
    (net (code "101") (name "unconnected-(HEADER7F-10-PadP$10)") (class "Default")
      (node (ref "HEADER7F") (pin "P$10") (pinfunction "10_P$10") (pintype "passive"))
    )
    (net (code "102") (name "unconnected-(HEADER7F-11-PadP$11)") (class "Default")
      (node (ref "HEADER7F") (pin "P$11") (pinfunction "11_P$11") (pintype "passive"))
    )
    (net (code "103") (name "unconnected-(HEADER7F-12-PadP$12)") (class "Default")
      (node (ref "HEADER7F") (pin "P$12") (pinfunction "12_P$12") (pintype "passive"))
    )
    (net (code "104") (name "unconnected-(HEADER7F-13-PadP$13)") (class "Default")
      (node (ref "HEADER7F") (pin "P$13") (pinfunction "13_P$13") (pintype "passive"))
    )
    (net (code "105") (name "unconnected-(HEADER7F-14-PadP$14)") (class "Default")
      (node (ref "HEADER7F") (pin "P$14") (pinfunction "14_P$14") (pintype "passive"))
    )
    (net (code "106") (name "unconnected-(HEADER7M-11-PadP$11)") (class "Default")
      (node (ref "HEADER7M") (pin "P$11") (pinfunction "11_P$11") (pintype "passive"))
    )
    (net (code "107") (name "unconnected-(HEADER7M-12-PadP$12)") (class "Default")
      (node (ref "HEADER7M") (pin "P$12") (pinfunction "12_P$12") (pintype "passive"))
    )
    (net (code "108") (name "unconnected-(HEADER9F-3-PadP$3)") (class "Default")
      (node (ref "HEADER9F") (pin "P$3") (pinfunction "3_P$3") (pintype "passive"))
    )
    (net (code "109") (name "unconnected-(HEADER9F-4-PadP$4)") (class "Default")
      (node (ref "HEADER9F") (pin "P$4") (pinfunction "4_P$4") (pintype "passive"))
    )
    (net (code "110") (name "unconnected-(HEADER9F-5-PadP$5)") (class "Default")
      (node (ref "HEADER9F") (pin "P$5") (pinfunction "5_P$5") (pintype "passive"))
    )
    (net (code "111") (name "unconnected-(HEADER9F-6-PadP$6)") (class "Default")
      (node (ref "HEADER9F") (pin "P$6") (pinfunction "6_P$6") (pintype "passive"))
    )
    (net (code "112") (name "unconnected-(HEADER9F-7-PadP$7)") (class "Default")
      (node (ref "HEADER9F") (pin "P$7") (pinfunction "7_P$7") (pintype "passive"))
    )
    (net (code "113") (name "unconnected-(HEADER9M-7-PadP$7)") (class "Default")
      (node (ref "HEADER9M") (pin "P$7") (pinfunction "7_P$7") (pintype "passive"))
    )
    (net (code "114") (name "unconnected-(MAG-NC-Pad3)") (class "Default")
      (node (ref "MAG") (pin "3") (pinfunction "NC_3") (pintype "bidirectional"))
    )
    (net (code "115") (name "unconnected-(MAG-NC-Pad5)") (class "Default")
      (node (ref "MAG") (pin "5") (pinfunction "NC_5") (pintype "bidirectional"))
    )
    (net (code "116") (name "unconnected-(MAG-NC-Pad6)") (class "Default")
      (node (ref "MAG") (pin "6") (pinfunction "NC_6") (pintype "bidirectional"))
    )
    (net (code "117") (name "unconnected-(MAG-NC-Pad7)") (class "Default")
      (node (ref "MAG") (pin "7") (pinfunction "NC_7") (pintype "bidirectional"))
    )
    (net (code "118") (name "unconnected-(MAG-NC-Pad14)") (class "Default")
      (node (ref "MAG") (pin "14") (pinfunction "NC_14") (pintype "bidirectional"))
    )
    (net (code "119") (name "unconnected-(SAM-ICE-Pad2)") (class "Default")
      (node (ref "SAM-ICE") (pin "2") (pinfunction "2_2") (pintype "passive"))
    )
    (net (code "120") (name "unconnected-(SAM-ICE-Pad3)") (class "Default")
      (node (ref "SAM-ICE") (pin "3") (pinfunction "3_3") (pintype "passive"))
    )
    (net (code "121") (name "unconnected-(SAM-ICE-Pad4)") (class "Default")
      (node (ref "SAM-ICE") (pin "4") (pinfunction "4_4") (pintype "passive"))
    )
    (net (code "122") (name "unconnected-(SAM-ICE-Pad5)") (class "Default")
      (node (ref "SAM-ICE") (pin "5") (pinfunction "5_5") (pintype "passive"))
    )
    (net (code "123") (name "unconnected-(SAM-ICE-Pad6)") (class "Default")
      (node (ref "SAM-ICE") (pin "6") (pinfunction "6_6") (pintype "passive"))
    )
    (net (code "124") (name "unconnected-(SAM-ICE-Pad8)") (class "Default")
      (node (ref "SAM-ICE") (pin "8") (pinfunction "8_8") (pintype "passive"))
    )
    (net (code "125") (name "unconnected-(SAM-ICE-Pad10)") (class "Default")
      (node (ref "SAM-ICE") (pin "10") (pinfunction "10_10") (pintype "passive"))
    )
    (net (code "126") (name "unconnected-(SAM-ICE-Pad11)") (class "Default")
      (node (ref "SAM-ICE") (pin "11") (pinfunction "11_11") (pintype "passive"))
    )
    (net (code "127") (name "unconnected-(SAM-ICE-Pad12)") (class "Default")
      (node (ref "SAM-ICE") (pin "12") (pinfunction "12_12") (pintype "passive"))
    )
    (net (code "128") (name "unconnected-(SAM-ICE-Pad13)") (class "Default")
      (node (ref "SAM-ICE") (pin "13") (pinfunction "13_13") (pintype "passive"))
    )
    (net (code "129") (name "unconnected-(SAM-ICE-Pad14)") (class "Default")
      (node (ref "SAM-ICE") (pin "14") (pinfunction "14_14") (pintype "passive"))
    )
    (net (code "130") (name "unconnected-(SAM-ICE-Pad16)") (class "Default")
      (node (ref "SAM-ICE") (pin "16") (pinfunction "16_16") (pintype "passive"))
    )
    (net (code "131") (name "unconnected-(SAM-ICE-Pad17)") (class "Default")
      (node (ref "SAM-ICE") (pin "17") (pinfunction "17_17") (pintype "passive"))
    )
    (net (code "132") (name "unconnected-(SAM-ICE-Pad18)") (class "Default")
      (node (ref "SAM-ICE") (pin "18") (pinfunction "18_18") (pintype "passive"))
    )
    (net (code "133") (name "unconnected-(SAM-ICE-Pad19)") (class "Default")
      (node (ref "SAM-ICE") (pin "19") (pinfunction "19_19") (pintype "passive"))
    )
    (net (code "134") (name "unconnected-(SAM-ICE-Pad20)") (class "Default")
      (node (ref "SAM-ICE") (pin "20") (pinfunction "20_20") (pintype "passive"))
    )
    (net (code "135") (name "unconnected-(U$2-CLR-Pad9)") (class "Default")
      (node (ref "U$2") (pin "9") (pinfunction "CLR_9") (pintype "bidirectional"))
    )
    (net (code "136") (name "unconnected-(UC1-PA02-PadP$3)") (class "Default")
      (node (ref "UC1") (pin "P$3") (pinfunction "PA02_P$3") (pintype "bidirectional"))
    )
    (net (code "137") (name "unconnected-(UC1-PA03-PadP$4)") (class "Default")
      (node (ref "UC1") (pin "P$4") (pinfunction "PA03_P$4") (pintype "bidirectional"))
    )
    (net (code "138") (name "unconnected-(UC1-PA07-PadP$16)") (class "Default")
      (node (ref "UC1") (pin "P$16") (pinfunction "PA07_P$16") (pintype "bidirectional"))
    )
    (net (code "139") (name "unconnected-(UC1-PA08-PadP$17)") (class "Default")
      (node (ref "UC1") (pin "P$17") (pinfunction "PA08_P$17") (pintype "bidirectional"))
    )
    (net (code "140") (name "unconnected-(UC1-PA09-PadP$18)") (class "Default")
      (node (ref "UC1") (pin "P$18") (pinfunction "PA09_P$18") (pintype "bidirectional"))
    )
    (net (code "141") (name "unconnected-(UC1-PA10-PadP$19)") (class "Default")
      (node (ref "UC1") (pin "P$19") (pinfunction "PA10_P$19") (pintype "bidirectional"))
    )
    (net (code "142") (name "unconnected-(UC1-PA11-PadP$20)") (class "Default")
      (node (ref "UC1") (pin "P$20") (pinfunction "PA11_P$20") (pintype "bidirectional"))
    )
    (net (code "143") (name "unconnected-(UC1-PA27-PadP$51)") (class "Default")
      (node (ref "UC1") (pin "P$51") (pinfunction "PA27_P$51") (pintype "bidirectional"))
    )
    (net (code "144") (name "unconnected-(UC1-PA28-PadP$53)") (class "Default")
      (node (ref "UC1") (pin "P$53") (pinfunction "PA28_P$53") (pintype "bidirectional"))
    )
    (net (code "145") (name "unconnected-(UC1-PB06-PadP$9)") (class "Default")
      (node (ref "UC1") (pin "P$9") (pinfunction "PB06_P$9") (pintype "bidirectional"))
    )
    (net (code "146") (name "unconnected-(UC1-PB10-PadP$23)") (class "Default")
      (node (ref "UC1") (pin "P$23") (pinfunction "PB10_P$23") (pintype "bidirectional"))
    )
    (net (code "147") (name "unconnected-(UC1-PB11-PadP$24)") (class "Default")
      (node (ref "UC1") (pin "P$24") (pinfunction "PB11_P$24") (pintype "bidirectional"))
    )
    (net (code "148") (name "unconnected-(UC1-PB12-PadP$25)") (class "Default")
      (node (ref "UC1") (pin "P$25") (pinfunction "PB12_P$25") (pintype "bidirectional"))
    )
    (net (code "149") (name "unconnected-(UC1-PB13-PadP$26)") (class "Default")
      (node (ref "UC1") (pin "P$26") (pinfunction "PB13_P$26") (pintype "bidirectional"))
    )
    (net (code "150") (name "unconnected-(UC1-PB14-PadP$27)") (class "Default")
      (node (ref "UC1") (pin "P$27") (pinfunction "PB14_P$27") (pintype "bidirectional"))
    )
    (net (code "151") (name "unconnected-(UC1-PB22-PadP$49)") (class "Default")
      (node (ref "UC1") (pin "P$49") (pinfunction "PB22_P$49") (pintype "bidirectional"))
    )
    (net (code "152") (name "unconnected-(UC1-PB23-PadP$50)") (class "Default")
      (node (ref "UC1") (pin "P$50") (pinfunction "PB23_P$50") (pintype "bidirectional"))
    )
    (net (code "153") (name "unconnected-(UC1-PB30-PadP$59)") (class "Default")
      (node (ref "UC1") (pin "P$59") (pinfunction "PB30_P$59") (pintype "bidirectional"))
    )
    (net (code "154") (name "unconnected-(UC1-PB31-PadP$60)") (class "Default")
      (node (ref "UC1") (pin "P$60") (pinfunction "PB31_P$60") (pintype "bidirectional"))
    )
  )
)
